# Manimohan05_Linear-Power-supply__Sheet_1.net
KiCad netlist of a schematic drawn in Altium Designer
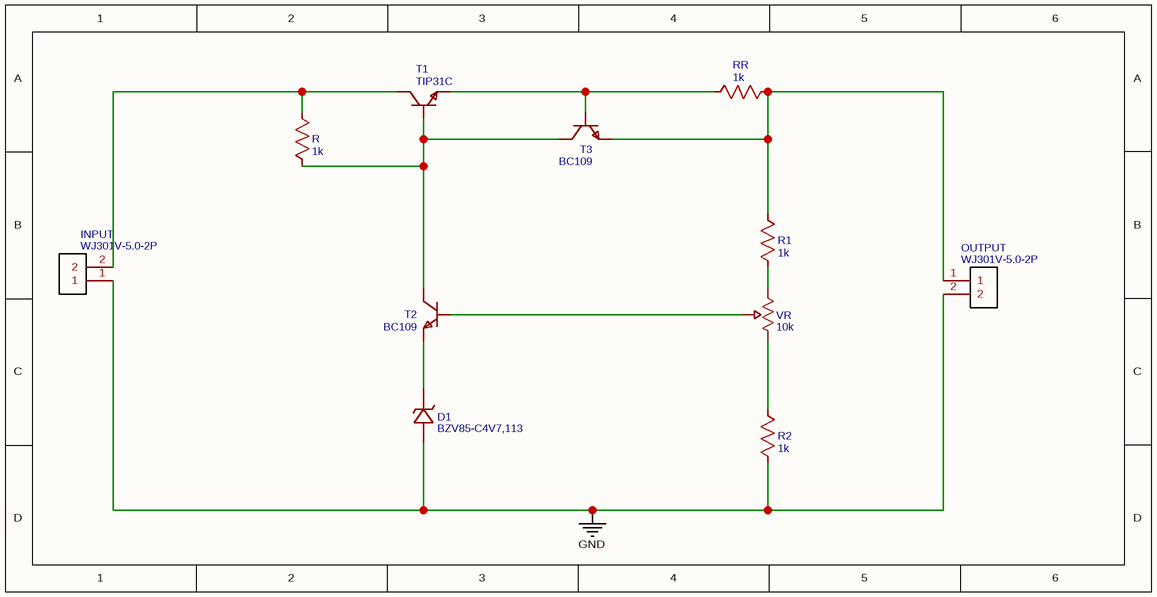
[diagram p0: Manimohan05_Linear-Power-supply__Sheet_1_2023-05-23.schdoc]

(export (version "E")
  (design (tool "Eeschema 10.0.6"))
  (components
    (comp (ref "D1")
      (value "BZV85-C4V7,113")
      (fields (field (name "BOM_SUPPLIER PART") "C550487") (field (name "CONTRIBUTOR") "LCSC"))
      (libsource (lib "altium-import") (part "root_3_BZV85-C4V7,113_"))
    )
    (comp (ref "INPUT")
      (value "WJ301V-5.0-2P")
      (fields (field (name "BOM_SUPPLIER PART") "C8475"))
      (libsource (lib "altium-import") (part "root_1_WJ301V-5.0-2P_"))
    )
    (comp (ref "OUTPUT")
      (value "WJ301V-5.0-2P")
      (fields (field (name "BOM_SUPPLIER PART") "C8475"))
      (libsource (lib "altium-import") (part "root_3_WJ301V-5.0-2P_"))
    )
    (comp (ref "R")
      (value "1k")
      (fields (field (name "CONTRIBUTOR") "LCEDA_Lib"))
      (libsource (lib "altium-import") (part "root_3_1k_"))
    )
    (comp (ref "R1")
      (value "1k")
      (fields (field (name "CONTRIBUTOR") "LCEDA_Lib"))
      (libsource (lib "altium-import") (part "root_3_1k_"))
    )
    (comp (ref "R2")
      (value "1k")
      (fields (field (name "CONTRIBUTOR") "LCEDA_Lib"))
      (libsource (lib "altium-import") (part "root_3_1k_"))
    )
    (comp (ref "RR")
      (value "1k")
      (fields (field (name "CONTRIBUTOR") "LCEDA_Lib"))
      (libsource (lib "altium-import") (part "root_0_1k_"))
    )
    (comp (ref "T1")
      (value "TIP31C")
      (fields (field (name "BOM_SUPPLIER PART") "C13506"))
      (libsource (lib "altium-import") (part "root_1_TIP31C_"))
    )
    (comp (ref "T2")
      (value "BC109")
      (fields (field (name "CONTRIBUTOR") "tcc.0292.2020"))
      (libsource (lib "altium-import") (part "root_0_BC109_"))
    )
    (comp (ref "T3")
      (value "BC109")
      (fields (field (name "CONTRIBUTOR") "tcc.0292.2020"))
      (libsource (lib "altium-import") (part "root_3_BC109_"))
    )
    (comp (ref "VR")
      (value "10k")
      (fields
        (field (name "POWER") "1/4W")
        (field (name "TOLERANCE") "±20%")
        (field (name "BOM_SUPPLIER PART") "3128548")
        (field (name "CONTRIBUTOR") "Prof. Ing. F. Scordino")
      )
      (libsource (lib "altium-import") (part "root_3_10k_"))
    )
  )
  (nets
    (net (code "1") (name "GND") (class "Default")
      (node (ref "D1") (pin "2") (pinfunction "A_2") (pintype "passive"))
      (node (ref "INPUT") (pin "1") (pinfunction "1_1") (pintype "passive"))
      (node (ref "OUTPUT") (pin "2") (pinfunction "2_2") (pintype "passive"))
      (node (ref "R2") (pin "2") (pinfunction "2_2") (pintype "passive"))
    )
    (net (code "2") (name "Net-(D1-K)") (class "Default")
      (node (ref "D1") (pin "1") (pinfunction "K_1") (pintype "passive"))
      (node (ref "T2") (pin "1") (pinfunction "E_1") (pintype "passive"))
    )
    (net (code "3") (name "Net-(R1-Pad2)") (class "Default")
      (node (ref "R1") (pin "2") (pinfunction "2_2") (pintype "passive"))
      (node (ref "VR") (pin "1") (pinfunction "1_1") (pintype "passive"))
    )
    (net (code "4") (name "Net-(R2-Pad1)") (class "Default")
      (node (ref "R2") (pin "1") (pinfunction "1_1") (pintype "passive"))
      (node (ref "VR") (pin "2") (pinfunction "2_2") (pintype "passive"))
    )
    (net (code "5") (name "Net-(T1-B)") (class "Default")
      (node (ref "R") (pin "2") (pinfunction "2_2") (pintype "passive"))
      (node (ref "T1") (pin "1") (pinfunction "B_1") (pintype "passive"))
      (node (ref "T2") (pin "3") (pinfunction "C_3") (pintype "passive"))
      (node (ref "T3") (pin "3") (pinfunction "C_3") (pintype "passive"))
    )
    (net (code "6") (name "Net-(T1-C)") (class "Default")
      (node (ref "INPUT") (pin "2") (pinfunction "2_2") (pintype "passive"))
      (node (ref "R") (pin "1") (pinfunction "1_1") (pintype "passive"))
      (node (ref "T1") (pin "2") (pinfunction "C_2") (pintype "passive"))
    )
    (net (code "7") (name "Net-(T1-E)") (class "Default")
      (node (ref "RR") (pin "1") (pinfunction "1_1") (pintype "passive"))
      (node (ref "T1") (pin "3") (pinfunction "E_3") (pintype "passive"))
      (node (ref "T3") (pin "2") (pinfunction "B_2") (pintype "passive"))
    )
    (net (code "8") (name "Net-(T2-B)") (class "Default")
      (node (ref "T2") (pin "2") (pinfunction "B_2") (pintype "passive"))
      (node (ref "VR") (pin "3") (pinfunction "3_3") (pintype "passive"))
    )
    (net (code "9") (name "Net-(T3-E)") (class "Default")
      (node (ref "OUTPUT") (pin "1") (pinfunction "1_1") (pintype "passive"))
      (node (ref "R1") (pin "1") (pinfunction "1_1") (pintype "passive"))
      (node (ref "RR") (pin "2") (pinfunction "2_2") (pintype "passive"))
      (node (ref "T3") (pin "1") (pinfunction "E_1") (pintype "passive"))
    )
  )
)
